# SchemaAction_Actionneurs.net
KiCad netlist of a schematic drawn in Altium Designer
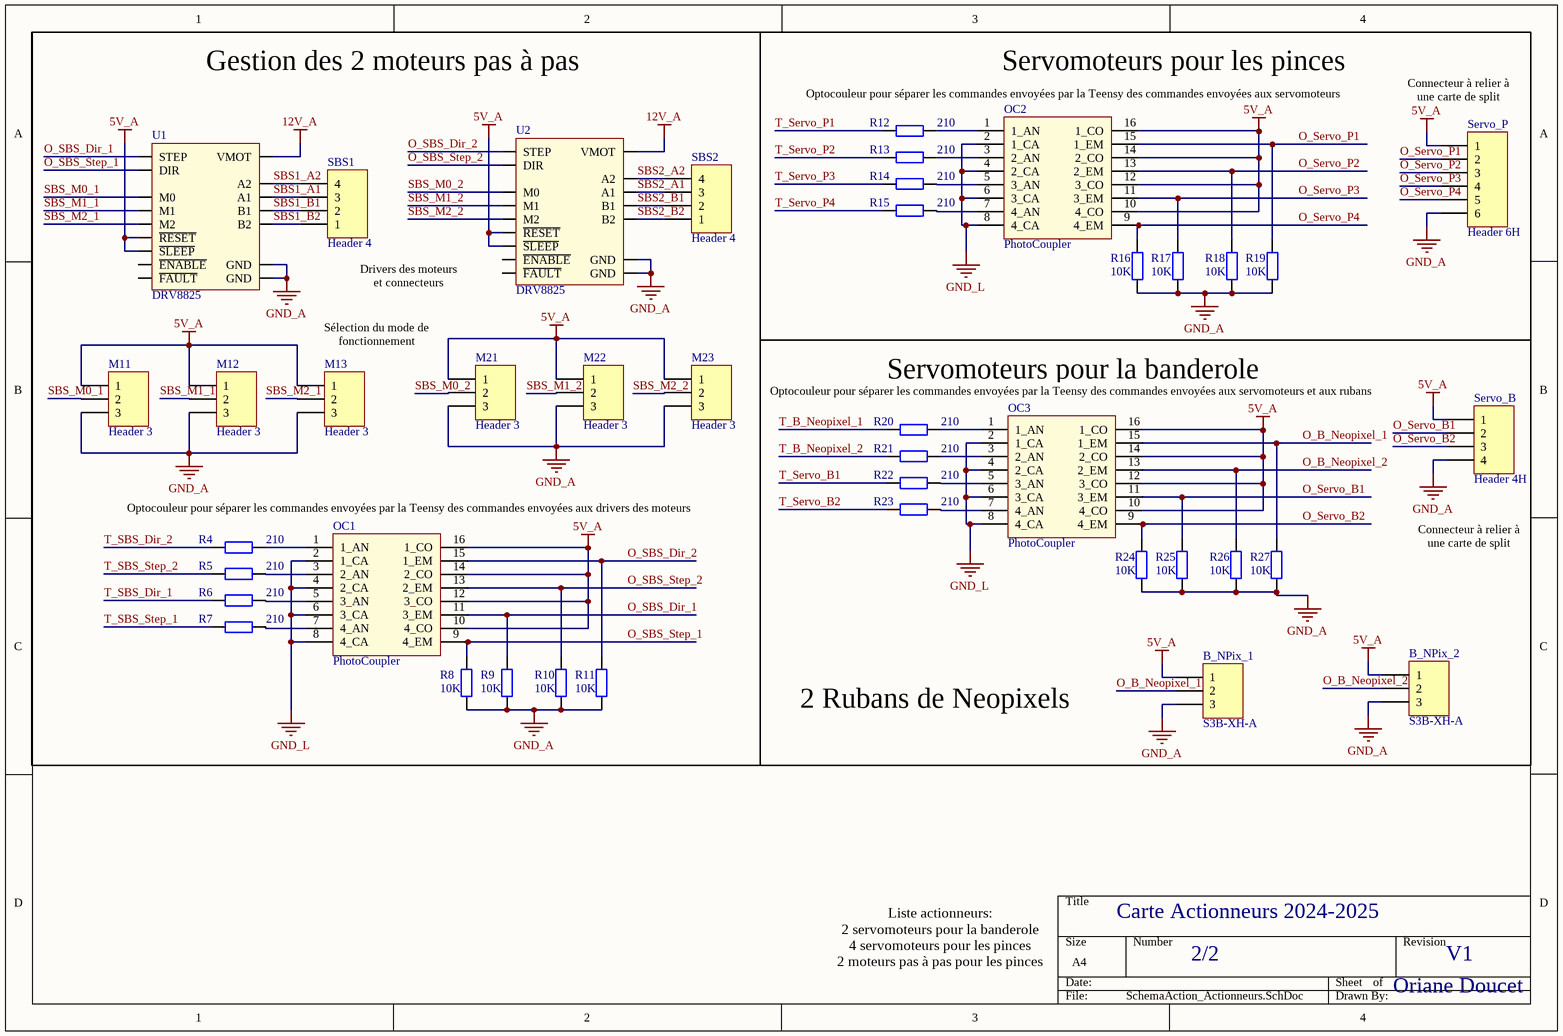
[diagram p0: SchemaAction_Actionneurs.SchDoc]

(export (version "E")
  (design (tool "Eeschema 10.0.6"))
  (components
    (comp (ref "B_NPix_1")
      (value "S3B-XH-A")
      (footprint "S3B-XH-A")
      (description "Header, 3-Pin, Right Angle")
      (fields (field (name "PUBLISHER") "Altium Limited"))
      (libsource (lib "Miscellaneous Connectors") (part "Header 3H"))
    )
    (comp (ref "B_NPix_2")
      (value "S3B-XH-A")
      (footprint "S3B-XH-A")
      (description "Header, 3-Pin, Right Angle")
      (fields (field (name "PUBLISHER") "Altium Limited"))
      (libsource (lib "Miscellaneous Connectors") (part "Header 3H"))
    )
    (comp (ref "M11")
      (value "Header 3")
      (footprint "HDR1X3")
      (description "Header, 3-Pin")
      (fields (field (name "PUBLISHER") "Altium Limited"))
      (libsource (lib "Miscellaneous Connectors") (part "Header 3"))
    )
    (comp (ref "M12")
      (value "Header 3")
      (footprint "HDR1X3")
      (description "Header, 3-Pin")
      (fields (field (name "PUBLISHER") "Altium Limited"))
      (libsource (lib "Miscellaneous Connectors") (part "Header 3"))
    )
    (comp (ref "M13")
      (value "Header 3")
      (footprint "HDR1X3")
      (description "Header, 3-Pin")
      (fields (field (name "PUBLISHER") "Altium Limited"))
      (libsource (lib "Miscellaneous Connectors") (part "Header 3"))
    )
    (comp (ref "M21")
      (value "Header 3")
      (footprint "HDR1X3")
      (description "Header, 3-Pin")
      (fields (field (name "PUBLISHER") "Altium Limited"))
      (libsource (lib "Miscellaneous Connectors") (part "Header 3"))
    )
    (comp (ref "M22")
      (value "Header 3")
      (footprint "HDR1X3")
      (description "Header, 3-Pin")
      (fields (field (name "PUBLISHER") "Altium Limited"))
      (libsource (lib "Miscellaneous Connectors") (part "Header 3"))
    )
    (comp (ref "M23")
      (value "Header 3")
      (footprint "HDR1X3")
      (description "Header, 3-Pin")
      (fields (field (name "PUBLISHER") "Altium Limited"))
      (libsource (lib "Miscellaneous Connectors") (part "Header 3"))
    )
    (comp (ref "OC1")
      (value "PhotoCoupler")
      (footprint "16 pins SOIC, TI")
      (description "Integrated Circuit")
      (fields
        (field (name "MANUFACTURER_PART_NUMBER") "LTV-247")
        (field (name "MOUSER PART NUMBER") "859-LTV-247")
      )
      (libsource (lib "SamacSys") (part "LTV-247"))
    )
    (comp (ref "OC2")
      (value "PhotoCoupler")
      (footprint "16 pins SOIC, TI")
      (description "Integrated Circuit")
      (fields
        (field (name "MANUFACTURER_PART_NUMBER") "LTV-247")
        (field (name "MOUSER PART NUMBER") "859-LTV-247")
      )
      (libsource (lib "SamacSys") (part "LTV-247"))
    )
    (comp (ref "OC3")
      (value "PhotoCoupler")
      (footprint "16 pins SOIC, TI")
      (description "Integrated Circuit")
      (fields
        (field (name "MANUFACTURER_PART_NUMBER") "LTV-247")
        (field (name "MOUSER PART NUMBER") "859-LTV-247")
      )
      (libsource (lib "SamacSys") (part "LTV-247"))
    )
    (comp (ref "R4")
      (value "210")
      (footprint "Resistor 1206")
      (description "Resistor")
      (fields (field (name "Comment") "Res2") (field (name "PUBLISHER") "Altium Limited"))
      (libsource (lib "Miscellaneous Devices") (part "Res2"))
    )
    (comp (ref "R5")
      (value "210")
      (footprint "Resistor 1206")
      (description "Resistor")
      (fields (field (name "Comment") "Res2") (field (name "PUBLISHER") "Altium Limited"))
      (libsource (lib "Miscellaneous Devices") (part "Res2"))
    )
    (comp (ref "R6")
      (value "210")
      (footprint "Resistor 1206")
      (description "Resistor")
      (fields (field (name "Comment") "Res2") (field (name "PUBLISHER") "Altium Limited"))
      (libsource (lib "Miscellaneous Devices") (part "Res2"))
    )
    (comp (ref "R7")
      (value "210")
      (footprint "Resistor 1206")
      (description "Resistor")
      (fields (field (name "Comment") "Res2") (field (name "PUBLISHER") "Altium Limited"))
      (libsource (lib "Miscellaneous Devices") (part "Res2"))
    )
    (comp (ref "R8")
      (value "10K")
      (footprint "Resistor 1206")
      (description "Resistor")
      (fields (field (name "Comment") "Res2") (field (name "PUBLISHER") "Altium Limited"))
      (libsource (lib "") (part "Res2_1"))
    )
    (comp (ref "R9")
      (value "10K")
      (footprint "Resistor 1206")
      (description "Resistor")
      (fields (field (name "Comment") "Res2") (field (name "PUBLISHER") "Altium Limited"))
      (libsource (lib "") (part "Res2_1"))
    )
    (comp (ref "R10")
      (value "10K")
      (footprint "Resistor 1206")
      (description "Resistor")
      (fields (field (name "Comment") "Res2") (field (name "PUBLISHER") "Altium Limited"))
      (libsource (lib "") (part "Res2_1"))
    )
    (comp (ref "R11")
      (value "10K")
      (footprint "Resistor 1206")
      (description "Resistor")
      (fields (field (name "Comment") "Res2") (field (name "PUBLISHER") "Altium Limited"))
      (libsource (lib "") (part "Res2_1"))
    )
    (comp (ref "R12")
      (value "210")
      (footprint "Resistor 1206")
      (description "Resistor")
      (fields (field (name "Comment") "Res2") (field (name "PUBLISHER") "Altium Limited"))
      (libsource (lib "Miscellaneous Devices") (part "Res2"))
    )
    (comp (ref "R13")
      (value "210")
      (footprint "Resistor 1206")
      (description "Resistor")
      (fields (field (name "Comment") "Res2") (field (name "PUBLISHER") "Altium Limited"))
      (libsource (lib "Miscellaneous Devices") (part "Res2"))
    )
    (comp (ref "R14")
      (value "210")
      (footprint "Resistor 1206")
      (description "Resistor")
      (fields (field (name "Comment") "Res2") (field (name "PUBLISHER") "Altium Limited"))
      (libsource (lib "Miscellaneous Devices") (part "Res2"))
    )
    (comp (ref "R15")
      (value "210")
      (footprint "Resistor 1206")
      (description "Resistor")
      (fields (field (name "Comment") "Res2") (field (name "PUBLISHER") "Altium Limited"))
      (libsource (lib "Miscellaneous Devices") (part "Res2"))
    )
    (comp (ref "R16")
      (value "10K")
      (footprint "Resistor 1206")
      (description "Resistor")
      (fields (field (name "Comment") "Res2") (field (name "PUBLISHER") "Altium Limited"))
      (libsource (lib "") (part "Res2_1"))
    )
    (comp (ref "R17")
      (value "10K")
      (footprint "Resistor 1206")
      (description "Resistor")
      (fields (field (name "Comment") "Res2") (field (name "PUBLISHER") "Altium Limited"))
      (libsource (lib "") (part "Res2_1"))
    )
    (comp (ref "R18")
      (value "10K")
      (footprint "Resistor 1206")
      (description "Resistor")
      (fields (field (name "Comment") "Res2") (field (name "PUBLISHER") "Altium Limited"))
      (libsource (lib "") (part "Res2_1"))
    )
    (comp (ref "R19")
      (value "10K")
      (footprint "Resistor 1206")
      (description "Resistor")
      (fields (field (name "Comment") "Res2") (field (name "PUBLISHER") "Altium Limited"))
      (libsource (lib "") (part "Res2_1"))
    )
    (comp (ref "R20")
      (value "210")
      (footprint "Resistor 1206")
      (description "Resistor")
      (fields (field (name "Comment") "Res2") (field (name "PUBLISHER") "Altium Limited"))
      (libsource (lib "Miscellaneous Devices") (part "Res2"))
    )
    (comp (ref "R21")
      (value "210")
      (footprint "Resistor 1206")
      (description "Resistor")
      (fields (field (name "Comment") "Res2") (field (name "PUBLISHER") "Altium Limited"))
      (libsource (lib "Miscellaneous Devices") (part "Res2"))
    )
    (comp (ref "R22")
      (value "210")
      (footprint "Resistor 1206")
      (description "Resistor")
      (fields (field (name "Comment") "Res2") (field (name "PUBLISHER") "Altium Limited"))
      (libsource (lib "Miscellaneous Devices") (part "Res2"))
    )
    (comp (ref "R23")
      (value "210")
      (footprint "Resistor 1206")
      (description "Resistor")
      (fields (field (name "Comment") "Res2") (field (name "PUBLISHER") "Altium Limited"))
      (libsource (lib "Miscellaneous Devices") (part "Res2"))
    )
    (comp (ref "R24")
      (value "10K")
      (footprint "Resistor 1206")
      (description "Resistor")
      (fields (field (name "Comment") "Res2") (field (name "PUBLISHER") "Altium Limited"))
      (libsource (lib "") (part "Res2_1"))
    )
    (comp (ref "R25")
      (value "10K")
      (footprint "Resistor 1206")
      (description "Resistor")
      (fields (field (name "Comment") "Res2") (field (name "PUBLISHER") "Altium Limited"))
      (libsource (lib "") (part "Res2_1"))
    )
    (comp (ref "R26")
      (value "10K")
      (footprint "Resistor 1206")
      (description "Resistor")
      (fields (field (name "Comment") "Res2") (field (name "PUBLISHER") "Altium Limited"))
      (libsource (lib "") (part "Res2_1"))
    )
    (comp (ref "R27")
      (value "10K")
      (footprint "Resistor 1206")
      (description "Resistor")
      (fields (field (name "Comment") "Res2") (field (name "PUBLISHER") "Altium Limited"))
      (libsource (lib "") (part "Res2_1"))
    )
    (comp (ref "SBS1")
      (value "Header 4")
      (footprint "S4B-XH-A")
      (description "Header, 4-Pin")
      (fields (field (name "PUBLISHER") "Altium Limited"))
      (libsource (lib "Miscellaneous Connectors") (part "Header 4"))
    )
    (comp (ref "SBS2")
      (value "Header 4")
      (footprint "S4B-XH-A")
      (description "Header, 4-Pin")
      (fields (field (name "PUBLISHER") "Altium Limited"))
      (libsource (lib "Miscellaneous Connectors") (part "Header 4"))
    )
    (comp (ref "Servo_B")
      (value "Header 4H")
      (footprint "S4B-XH-A")
      (description "Header, 4-Pin, Right Angle")
      (fields (field (name "PUBLISHER") "Altium Limited"))
      (libsource (lib "Miscellaneous Connectors") (part "Header 4H"))
    )
    (comp (ref "Servo_P")
      (value "Header 6H")
      (footprint "S6B-XH-A")
      (description "Header, 6-Pin, Right Angle")
      (fields (field (name "PUBLISHER") "Altium Limited"))
      (libsource (lib "Miscellaneous Connectors") (part "Header 6H"))
    )
    (comp (ref "U1")
      (value "DRV8825")
      (footprint "DRV8825")
      (description "Stepper Driver Module")
      (libsource (lib "SupaeroRobot") (part "DRV8825"))
    )
    (comp (ref "U2")
      (value "DRV8825")
      (footprint "DRV8825")
      (description "Stepper Driver Module")
      (libsource (lib "SupaeroRobot") (part "DRV8825"))
    )
  )
  (nets
    (net (code "1") (name "/O_B_Neopixel_1") (class "Default")
      (node (ref "B_NPix_1") (pin "2") (pinfunction "2_2") (pintype "passive"))
      (node (ref "OC3") (pin "15") (pinfunction "1_EM_15") (pintype "passive"))
      (node (ref "R27") (pin "2") (pinfunction "2_2") (pintype "passive"))
    )
    (net (code "2") (name "/O_B_Neopixel_2") (class "Default")
      (node (ref "B_NPix_2") (pin "2") (pinfunction "2_2") (pintype "passive"))
      (node (ref "OC3") (pin "13") (pinfunction "2_EM_13") (pintype "passive"))
      (node (ref "R26") (pin "2") (pinfunction "2_2") (pintype "passive"))
    )
    (net (code "3") (name "/O_SBS_Dir_1") (class "Default")
      (node (ref "OC1") (pin "11") (pinfunction "3_EM_11") (pintype "passive"))
      (node (ref "R9") (pin "2") (pinfunction "2_2") (pintype "passive"))
      (node (ref "U1") (pin "7") (pinfunction "STEP_7") (pintype "passive"))
    )
    (net (code "4") (name "/O_SBS_Dir_2") (class "Default")
      (node (ref "OC1") (pin "15") (pinfunction "1_EM_15") (pintype "passive"))
      (node (ref "R11") (pin "2") (pinfunction "2_2") (pintype "passive"))
      (node (ref "U2") (pin "7") (pinfunction "STEP_7") (pintype "passive"))
    )
    (net (code "5") (name "/O_SBS_Step_1") (class "Default")
      (node (ref "OC1") (pin "9") (pinfunction "4_EM_9") (pintype "passive"))
      (node (ref "R8") (pin "2") (pinfunction "2_2") (pintype "passive"))
      (node (ref "U1") (pin "8") (pinfunction "DIR_8") (pintype "passive"))
    )
    (net (code "6") (name "/O_SBS_Step_2") (class "Default")
      (node (ref "OC1") (pin "13") (pinfunction "2_EM_13") (pintype "passive"))
      (node (ref "R10") (pin "2") (pinfunction "2_2") (pintype "passive"))
      (node (ref "U2") (pin "8") (pinfunction "DIR_8") (pintype "passive"))
    )
    (net (code "7") (name "/O_Servo_B1") (class "Default")
      (node (ref "OC3") (pin "11") (pinfunction "3_EM_11") (pintype "passive"))
      (node (ref "R25") (pin "2") (pinfunction "2_2") (pintype "passive"))
      (node (ref "Servo_B") (pin "2") (pinfunction "2_2") (pintype "passive"))
    )
    (net (code "8") (name "/O_Servo_B2") (class "Default")
      (node (ref "OC3") (pin "9") (pinfunction "4_EM_9") (pintype "passive"))
      (node (ref "R24") (pin "2") (pinfunction "2_2") (pintype "passive"))
      (node (ref "Servo_B") (pin "3") (pinfunction "3_3") (pintype "passive"))
    )
    (net (code "9") (name "/O_Servo_P1") (class "Default")
      (node (ref "OC2") (pin "15") (pinfunction "1_EM_15") (pintype "passive"))
      (node (ref "R19") (pin "2") (pinfunction "2_2") (pintype "passive"))
      (node (ref "Servo_P") (pin "2") (pinfunction "2_2") (pintype "passive"))
    )
    (net (code "10") (name "/O_Servo_P2") (class "Default")
      (node (ref "OC2") (pin "13") (pinfunction "2_EM_13") (pintype "passive"))
      (node (ref "R18") (pin "2") (pinfunction "2_2") (pintype "passive"))
      (node (ref "Servo_P") (pin "3") (pinfunction "3_3") (pintype "passive"))
    )
    (net (code "11") (name "/O_Servo_P3") (class "Default")
      (node (ref "OC2") (pin "11") (pinfunction "3_EM_11") (pintype "passive"))
      (node (ref "R17") (pin "2") (pinfunction "2_2") (pintype "passive"))
      (node (ref "Servo_P") (pin "4") (pinfunction "4_4") (pintype "passive"))
    )
    (net (code "12") (name "/O_Servo_P4") (class "Default")
      (node (ref "OC2") (pin "9") (pinfunction "4_EM_9") (pintype "passive"))
      (node (ref "R16") (pin "2") (pinfunction "2_2") (pintype "passive"))
      (node (ref "Servo_P") (pin "5") (pinfunction "5_5") (pintype "passive"))
    )
    (net (code "13") (name "/SBS1_A1") (class "Default")
      (node (ref "SBS1") (pin "3") (pinfunction "3_3") (pintype "passive"))
      (node (ref "U1") (pin "12") (pinfunction "A1_12") (pintype "passive"))
    )
    (net (code "14") (name "/SBS1_A2") (class "Default")
      (node (ref "SBS1") (pin "4") (pinfunction "4_4") (pintype "passive"))
      (node (ref "U1") (pin "11") (pinfunction "A2_11") (pintype "passive"))
    )
    (net (code "15") (name "/SBS1_B1") (class "Default")
      (node (ref "SBS1") (pin "2") (pinfunction "2_2") (pintype "passive"))
      (node (ref "U1") (pin "13") (pinfunction "B1_13") (pintype "passive"))
    )
    (net (code "16") (name "/SBS1_B2") (class "Default")
      (node (ref "SBS1") (pin "1") (pinfunction "1_1") (pintype "passive"))
      (node (ref "U1") (pin "14") (pinfunction "B2_14") (pintype "passive"))
    )
    (net (code "17") (name "/SBS2_A1") (class "Default")
      (node (ref "SBS2") (pin "3") (pinfunction "3_3") (pintype "passive"))
      (node (ref "U2") (pin "12") (pinfunction "A1_12") (pintype "passive"))
    )
    (net (code "18") (name "/SBS2_A2") (class "Default")
      (node (ref "SBS2") (pin "4") (pinfunction "4_4") (pintype "passive"))
      (node (ref "U2") (pin "11") (pinfunction "A2_11") (pintype "passive"))
    )
    (net (code "19") (name "/SBS2_B1") (class "Default")
      (node (ref "SBS2") (pin "2") (pinfunction "2_2") (pintype "passive"))
      (node (ref "U2") (pin "13") (pinfunction "B1_13") (pintype "passive"))
    )
    (net (code "20") (name "/SBS2_B2") (class "Default")
      (node (ref "SBS2") (pin "1") (pinfunction "1_1") (pintype "passive"))
      (node (ref "U2") (pin "14") (pinfunction "B2_14") (pintype "passive"))
    )
    (net (code "21") (name "/SBS_M0_1") (class "Default")
      (node (ref "M11") (pin "2") (pinfunction "2_2") (pintype "passive"))
      (node (ref "U1") (pin "2") (pinfunction "M0_2") (pintype "passive"))
    )
    (net (code "22") (name "/SBS_M0_2") (class "Default")
      (node (ref "M21") (pin "2") (pinfunction "2_2") (pintype "passive"))
      (node (ref "U2") (pin "2") (pinfunction "M0_2") (pintype "passive"))
    )
    (net (code "23") (name "/SBS_M1_1") (class "Default")
      (node (ref "M12") (pin "2") (pinfunction "2_2") (pintype "passive"))
      (node (ref "U1") (pin "3") (pinfunction "M1_3") (pintype "passive"))
    )
    (net (code "24") (name "/SBS_M1_2") (class "Default")
      (node (ref "M22") (pin "2") (pinfunction "2_2") (pintype "passive"))
      (node (ref "U2") (pin "3") (pinfunction "M1_3") (pintype "passive"))
    )
    (net (code "25") (name "/SBS_M2_1") (class "Default")
      (node (ref "M13") (pin "2") (pinfunction "2_2") (pintype "passive"))
      (node (ref "U1") (pin "4") (pinfunction "M2_4") (pintype "passive"))
    )
    (net (code "26") (name "/SBS_M2_2") (class "Default")
      (node (ref "M23") (pin "2") (pinfunction "2_2") (pintype "passive"))
      (node (ref "U2") (pin "4") (pinfunction "M2_4") (pintype "passive"))
    )
    (net (code "27") (name "/T_B_Neopixel_1") (class "Default")
      (node (ref "R20") (pin "2") (pinfunction "2_2") (pintype "passive"))
    )
    (net (code "28") (name "/T_B_Neopixel_2") (class "Default")
      (node (ref "R21") (pin "2") (pinfunction "2_2") (pintype "passive"))
    )
    (net (code "29") (name "/T_SBS_Dir_1") (class "Default")
      (node (ref "R6") (pin "2") (pinfunction "2_2") (pintype "passive"))
    )
    (net (code "30") (name "/T_SBS_Dir_2") (class "Default")
      (node (ref "R4") (pin "2") (pinfunction "2_2") (pintype "passive"))
    )
    (net (code "31") (name "/T_SBS_Step_1") (class "Default")
      (node (ref "R7") (pin "2") (pinfunction "2_2") (pintype "passive"))
    )
    (net (code "32") (name "/T_SBS_Step_2") (class "Default")
      (node (ref "R5") (pin "2") (pinfunction "2_2") (pintype "passive"))
    )
    (net (code "33") (name "/T_Servo_B1") (class "Default")
      (node (ref "R22") (pin "2") (pinfunction "2_2") (pintype "passive"))
    )
    (net (code "34") (name "/T_Servo_B2") (class "Default")
      (node (ref "R23") (pin "2") (pinfunction "2_2") (pintype "passive"))
    )
    (net (code "35") (name "/T_Servo_P1") (class "Default")
      (node (ref "R12") (pin "2") (pinfunction "2_2") (pintype "passive"))
    )
    (net (code "36") (name "/T_Servo_P2") (class "Default")
      (node (ref "R13") (pin "2") (pinfunction "2_2") (pintype "passive"))
    )
    (net (code "37") (name "/T_Servo_P3") (class "Default")
      (node (ref "R14") (pin "2") (pinfunction "2_2") (pintype "passive"))
    )
    (net (code "38") (name "/T_Servo_P4") (class "Default")
      (node (ref "R15") (pin "2") (pinfunction "2_2") (pintype "passive"))
    )
    (net (code "39") (name "5V_A") (class "Default")
      (node (ref "B_NPix_1") (pin "1") (pinfunction "1_1") (pintype "passive"))
      (node (ref "B_NPix_2") (pin "1") (pinfunction "1_1") (pintype "passive"))
      (node (ref "M11") (pin "1") (pinfunction "1_1") (pintype "passive"))
      (node (ref "M12") (pin "1") (pinfunction "1_1") (pintype "passive"))
      (node (ref "M13") (pin "1") (pinfunction "1_1") (pintype "passive"))
      (node (ref "M21") (pin "1") (pinfunction "1_1") (pintype "passive"))
      (node (ref "M22") (pin "1") (pinfunction "1_1") (pintype "passive"))
      (node (ref "M23") (pin "1") (pinfunction "1_1") (pintype "passive"))
      (node (ref "OC1") (pin "10") (pinfunction "4_CO_10") (pintype "passive"))
      (node (ref "OC1") (pin "12") (pinfunction "3_CO_12") (pintype "passive"))
      (node (ref "OC1") (pin "14") (pinfunction "2_CO_14") (pintype "passive"))
      (node (ref "OC1") (pin "16") (pinfunction "1_CO_16") (pintype "passive"))
      (node (ref "OC2") (pin "10") (pinfunction "4_CO_10") (pintype "passive"))
      (node (ref "OC2") (pin "12") (pinfunction "3_CO_12") (pintype "passive"))
      (node (ref "OC2") (pin "14") (pinfunction "2_CO_14") (pintype "passive"))
      (node (ref "OC2") (pin "16") (pinfunction "1_CO_16") (pintype "passive"))
      (node (ref "OC3") (pin "10") (pinfunction "4_CO_10") (pintype "passive"))
      (node (ref "OC3") (pin "12") (pinfunction "3_CO_12") (pintype "passive"))
      (node (ref "OC3") (pin "14") (pinfunction "2_CO_14") (pintype "passive"))
      (node (ref "OC3") (pin "16") (pinfunction "1_CO_16") (pintype "passive"))
      (node (ref "Servo_B") (pin "1") (pinfunction "1_1") (pintype "passive"))
      (node (ref "Servo_P") (pin "1") (pinfunction "1_1") (pintype "passive"))
      (node (ref "U1") (pin "5") (pinfunction "~{RESET}_5") (pintype "passive"))
      (node (ref "U1") (pin "6") (pinfunction "~{SLEEP}_6") (pintype "passive"))
      (node (ref "U2") (pin "5") (pinfunction "~{RESET}_5") (pintype "passive"))
      (node (ref "U2") (pin "6") (pinfunction "~{SLEEP}_6") (pintype "passive"))
    )
    (net (code "40") (name "12V_A") (class "Default")
      (node (ref "U1") (pin "16") (pinfunction "VMOT_16") (pintype "passive"))
      (node (ref "U2") (pin "16") (pinfunction "VMOT_16") (pintype "passive"))
    )
    (net (code "41") (name "GND_A") (class "Default")
      (node (ref "B_NPix_1") (pin "3") (pinfunction "3_3") (pintype "passive"))
      (node (ref "B_NPix_2") (pin "3") (pinfunction "3_3") (pintype "passive"))
      (node (ref "M11") (pin "3") (pinfunction "3_3") (pintype "passive"))
      (node (ref "M12") (pin "3") (pinfunction "3_3") (pintype "passive"))
      (node (ref "M13") (pin "3") (pinfunction "3_3") (pintype "passive"))
      (node (ref "M21") (pin "3") (pinfunction "3_3") (pintype "passive"))
      (node (ref "M22") (pin "3") (pinfunction "3_3") (pintype "passive"))
      (node (ref "M23") (pin "3") (pinfunction "3_3") (pintype "passive"))
      (node (ref "R10") (pin "1") (pinfunction "1_1") (pintype "passive"))
      (node (ref "R11") (pin "1") (pinfunction "1_1") (pintype "passive"))
      (node (ref "R16") (pin "1") (pinfunction "1_1") (pintype "passive"))
      (node (ref "R17") (pin "1") (pinfunction "1_1") (pintype "passive"))
      (node (ref "R18") (pin "1") (pinfunction "1_1") (pintype "passive"))
      (node (ref "R19") (pin "1") (pinfunction "1_1") (pintype "passive"))
      (node (ref "R24") (pin "1") (pinfunction "1_1") (pintype "passive"))
      (node (ref "R25") (pin "1") (pinfunction "1_1") (pintype "passive"))
      (node (ref "R26") (pin "1") (pinfunction "1_1") (pintype "passive"))
      (node (ref "R27") (pin "1") (pinfunction "1_1") (pintype "passive"))
      (node (ref "R8") (pin "1") (pinfunction "1_1") (pintype "passive"))
      (node (ref "R9") (pin "1") (pinfunction "1_1") (pintype "passive"))
      (node (ref "Servo_B") (pin "4") (pinfunction "4_4") (pintype "passive"))
      (node (ref "Servo_P") (pin "6") (pinfunction "6_6") (pintype "passive"))
      (node (ref "U1") (pin "15") (pinfunction "GND_15") (pintype "passive"))
      (node (ref "U1") (pin "9") (pinfunction "GND_9") (pintype "passive"))
      (node (ref "U2") (pin "15") (pinfunction "GND_15") (pintype "passive"))
      (node (ref "U2") (pin "9") (pinfunction "GND_9") (pintype "passive"))
    )
    (net (code "42") (name "GND_L") (class "Default")
      (node (ref "OC1") (pin "2") (pinfunction "1_CA_2") (pintype "passive"))
      (node (ref "OC1") (pin "4") (pinfunction "2_CA_4") (pintype "passive"))
      (node (ref "OC1") (pin "6") (pinfunction "3_CA_6") (pintype "passive"))
      (node (ref "OC1") (pin "8") (pinfunction "4_CA_8") (pintype "passive"))
      (node (ref "OC2") (pin "2") (pinfunction "1_CA_2") (pintype "passive"))
      (node (ref "OC2") (pin "4") (pinfunction "2_CA_4") (pintype "passive"))
      (node (ref "OC2") (pin "6") (pinfunction "3_CA_6") (pintype "passive"))
      (node (ref "OC2") (pin "8") (pinfunction "4_CA_8") (pintype "passive"))
      (node (ref "OC3") (pin "2") (pinfunction "1_CA_2") (pintype "passive"))
      (node (ref "OC3") (pin "4") (pinfunction "2_CA_4") (pintype "passive"))
      (node (ref "OC3") (pin "6") (pinfunction "3_CA_6") (pintype "passive"))
      (node (ref "OC3") (pin "8") (pinfunction "4_CA_8") (pintype "passive"))
    )
    (net (code "43") (name "Net-(OC1-1_AN)") (class "Default")
      (node (ref "OC1") (pin "1") (pinfunction "1_AN_1") (pintype "passive"))
      (node (ref "R4") (pin "1") (pinfunction "1_1") (pintype "passive"))
    )
    (net (code "44") (name "Net-(OC1-2_AN)") (class "Default")
      (node (ref "OC1") (pin "3") (pinfunction "2_AN_3") (pintype "passive"))
      (node (ref "R5") (pin "1") (pinfunction "1_1") (pintype "passive"))
    )
    (net (code "45") (name "Net-(OC1-3_AN)") (class "Default")
      (node (ref "OC1") (pin "5") (pinfunction "3_AN_5") (pintype "passive"))
      (node (ref "R6") (pin "1") (pinfunction "1_1") (pintype "passive"))
    )
    (net (code "46") (name "Net-(OC1-4_AN)") (class "Default")
      (node (ref "OC1") (pin "7") (pinfunction "4_AN_7") (pintype "passive"))
      (node (ref "R7") (pin "1") (pinfunction "1_1") (pintype "passive"))
    )
    (net (code "47") (name "Net-(OC2-1_AN)") (class "Default")
      (node (ref "OC2") (pin "1") (pinfunction "1_AN_1") (pintype "passive"))
      (node (ref "R12") (pin "1") (pinfunction "1_1") (pintype "passive"))
    )
    (net (code "48") (name "Net-(OC2-2_AN)") (class "Default")
      (node (ref "OC2") (pin "3") (pinfunction "2_AN_3") (pintype "passive"))
      (node (ref "R13") (pin "1") (pinfunction "1_1") (pintype "passive"))
    )
    (net (code "49") (name "Net-(OC2-3_AN)") (class "Default")
      (node (ref "OC2") (pin "5") (pinfunction "3_AN_5") (pintype "passive"))
      (node (ref "R14") (pin "1") (pinfunction "1_1") (pintype "passive"))
    )
    (net (code "50") (name "Net-(OC2-4_AN)") (class "Default")
      (node (ref "OC2") (pin "7") (pinfunction "4_AN_7") (pintype "passive"))
      (node (ref "R15") (pin "1") (pinfunction "1_1") (pintype "passive"))
    )
    (net (code "51") (name "Net-(OC3-1_AN)") (class "Default")
      (node (ref "OC3") (pin "1") (pinfunction "1_AN_1") (pintype "passive"))
      (node (ref "R20") (pin "1") (pinfunction "1_1") (pintype "passive"))
    )
    (net (code "52") (name "Net-(OC3-2_AN)") (class "Default")
      (node (ref "OC3") (pin "3") (pinfunction "2_AN_3") (pintype "passive"))
      (node (ref "R21") (pin "1") (pinfunction "1_1") (pintype "passive"))
    )
    (net (code "53") (name "Net-(OC3-3_AN)") (class "Default")
      (node (ref "OC3") (pin "5") (pinfunction "3_AN_5") (pintype "passive"))
      (node (ref "R22") (pin "1") (pinfunction "1_1") (pintype "passive"))
    )
    (net (code "54") (name "Net-(OC3-4_AN)") (class "Default")
      (node (ref "OC3") (pin "7") (pinfunction "4_AN_7") (pintype "passive"))
      (node (ref "R23") (pin "1") (pinfunction "1_1") (pintype "passive"))
    )
    (net (code "55") (name "unconnected-(U1-~{ENABLE}-Pad1)") (class "Default")
      (node (ref "U1") (pin "1") (pinfunction "~{ENABLE}_1") (pintype "passive"))
    )
    (net (code "56") (name "unconnected-(U1-~{FAULT}-Pad10)") (class "Default")
      (node (ref "U1") (pin "10") (pinfunction "~{FAULT}_10") (pintype "passive"))
    )
    (net (code "57") (name "unconnected-(U2-~{ENABLE}-Pad1)") (class "Default")
      (node (ref "U2") (pin "1") (pinfunction "~{ENABLE}_1") (pintype "passive"))
    )
    (net (code "58") (name "unconnected-(U2-~{FAULT}-Pad10)") (class "Default")
      (node (ref "U2") (pin "10") (pinfunction "~{FAULT}_10") (pintype "passive"))
    )
  )
)
